# Comunicacao.net
KiCad netlist of a schematic drawn in Altium Designer
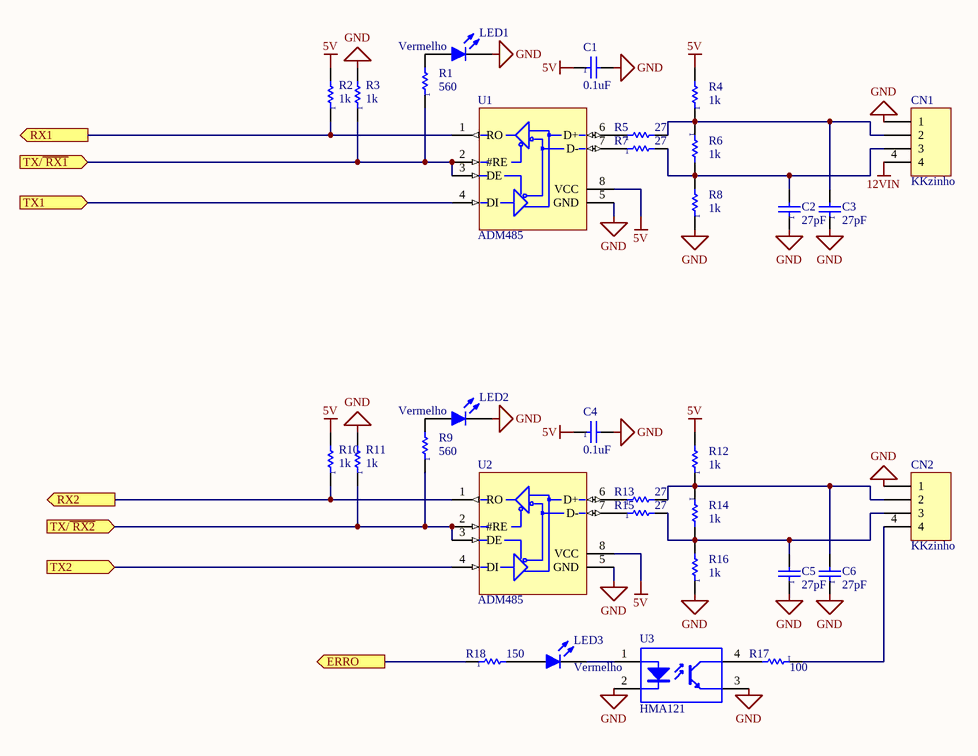
[diagram p0: Comunicacao.SchDoc]

(export (version "E")
  (design (tool "Eeschema 10.0.6"))
  (components
    (comp (ref "C1")
      (value "0.1uF")
      (footprint "SMD_0805")
      (description "Capacitor")
      (fields (field (name "MANUFACTURER") "Generic Components"))
      (libsource (lib "comps_passivos") (part "Cap"))
    )
    (comp (ref "C2")
      (value "27pF")
      (footprint "SMD_0805")
      (description "Capacitor")
      (fields (field (name "MANUFACTURER") "Generic Components"))
      (libsource (lib "comps_passivos") (part "Cap"))
    )
    (comp (ref "C3")
      (value "27pF")
      (footprint "SMD_0805")
      (description "Capacitor")
      (fields (field (name "MANUFACTURER") "Generic Components"))
      (libsource (lib "comps_passivos") (part "Cap"))
    )
    (comp (ref "C4")
      (value "0.1uF")
      (footprint "SMD_0805")
      (description "Capacitor")
      (fields (field (name "MANUFACTURER") "Generic Components"))
      (libsource (lib "comps_passivos") (part "Cap"))
    )
    (comp (ref "C5")
      (value "27pF")
      (footprint "SMD_0805")
      (description "Capacitor")
      (fields (field (name "MANUFACTURER") "Generic Components"))
      (libsource (lib "comps_passivos") (part "Cap"))
    )
    (comp (ref "C6")
      (value "27pF")
      (footprint "SMD_0805")
      (description "Capacitor")
      (fields (field (name "MANUFACTURER") "Generic Components"))
      (libsource (lib "comps_passivos") (part "Cap"))
    )
    (comp (ref "CN1")
      (value "KKzinho")
      (footprint "KK4 - 2.54mm")
      (description "Conector Linear tipo KK de 4 vias")
      (libsource (lib "conectores") (part "KK4"))
    )
    (comp (ref "CN2")
      (value "KKzinho")
      (footprint "KK4 - 2.54mm")
      (description "Conector Linear tipo KK de 4 vias")
      (libsource (lib "conectores") (part "KK4"))
    )
    (comp (ref "LED1")
      (value "Vermelho")
      (footprint "LED_SMD_0805")
      (description "Led")
      (fields (field (name "MANUFACTURER") "Generic Components") (field (name "PUBLISHER") "Altium Limited"))
      (libsource (lib "diodos_transistores") (part "Led"))
    )
    (comp (ref "LED2")
      (value "Vermelho")
      (footprint "LED_SMD_0805")
      (description "Led")
      (fields (field (name "MANUFACTURER") "Generic Components") (field (name "PUBLISHER") "Altium Limited"))
      (libsource (lib "diodos_transistores") (part "Led"))
    )
    (comp (ref "LED3")
      (value "Vermelho")
      (footprint "LED_SMD_0805")
      (description "Led")
      (fields (field (name "MANUFACTURER") "Generic Components") (field (name "PUBLISHER") "Altium Limited"))
      (libsource (lib "diodos_transistores") (part "Led"))
    )
    (comp (ref "R1")
      (value "560")
      (footprint "SMD_0805")
      (description "Resistor")
      (libsource (lib "passivos") (part "Res"))
    )
    (comp (ref "R2")
      (value "1k")
      (footprint "SMD_0805")
      (description "Resistor")
      (libsource (lib "passivos") (part "Res"))
    )
    (comp (ref "R3")
      (value "1k")
      (footprint "SMD_0805")
      (description "Resistor")
      (libsource (lib "passivos") (part "Resistor"))
    )
    (comp (ref "R4")
      (value "1k")
      (footprint "SMD_0805")
      (description "Resistor")
      (libsource (lib "passivos") (part "Resistor"))
    )
    (comp (ref "R5")
      (value "27")
      (footprint "SMD_0805")
      (description "Resistor")
      (libsource (lib "passivos") (part "Resistor"))
    )
    (comp (ref "R6")
      (value "1k")
      (footprint "SMD_0805")
      (description "Resistor")
      (libsource (lib "passivos") (part "Resistor"))
    )
    (comp (ref "R7")
      (value "27")
      (footprint "SMD_0805")
      (description "Resistor")
      (libsource (lib "passivos") (part "Resistor"))
    )
    (comp (ref "R8")
      (value "1k")
      (footprint "SMD_0805")
      (description "Resistor")
      (libsource (lib "passivos") (part "Resistor"))
    )
    (comp (ref "R9")
      (value "560")
      (footprint "SMD_0805")
      (description "Resistor")
      (libsource (lib "passivos") (part "Res"))
    )
    (comp (ref "R10")
      (value "1k")
      (footprint "SMD_0805")
      (description "Resistor")
      (libsource (lib "passivos") (part "Res"))
    )
    (comp (ref "R11")
      (value "1k")
      (footprint "SMD_0805")
      (description "Resistor")
      (libsource (lib "passivos") (part "Resistor"))
    )
    (comp (ref "R12")
      (value "1k")
      (footprint "SMD_0805")
      (description "Resistor")
      (libsource (lib "passivos") (part "Resistor"))
    )
    (comp (ref "R13")
      (value "27")
      (footprint "SMD_0805")
      (description "Resistor")
      (libsource (lib "passivos") (part "Resistor"))
    )
    (comp (ref "R14")
      (value "1k")
      (footprint "SMD_0805")
      (description "Resistor")
      (libsource (lib "passivos") (part "Resistor"))
    )
    (comp (ref "R15")
      (value "27")
      (footprint "SMD_0805")
      (description "Resistor")
      (libsource (lib "passivos") (part "Resistor"))
    )
    (comp (ref "R16")
      (value "1k")
      (footprint "SMD_0805")
      (description "Resistor")
      (libsource (lib "passivos") (part "Resistor"))
    )
    (comp (ref "R17")
      (value "100")
      (footprint "SMD_0805")
      (description "Resistor")
      (libsource (lib "passivos") (part "Resistor"))
    )
    (comp (ref "R18")
      (value "150")
      (footprint "SMD_0805")
      (description "Resistor")
      (libsource (lib "passivos") (part "Resistor"))
    )
    (comp (ref "U1")
      (value "ADM485")
      (footprint "SO-8_SO-G8/E2.5")
      (description "Differential bus transceiver (MAX485 - SN75176)")
      (libsource (lib "cis_digitais") (part "RS485"))
    )
    (comp (ref "U2")
      (value "ADM485")
      (footprint "SO-8_SO-G8/E2.5")
      (description "Differential bus transceiver (MAX485 - SN75176)")
      (libsource (lib "cis_digitais") (part "RS485"))
    )
    (comp (ref "U3")
      (value "HMA121")
      (footprint "SO4")
      (description "Phototransistor Optocoupler SMD full Pptch mini-flat type")
      (fields (field (name "MANUFACTURER") "Generic Components") (field (name "PUBLISHER") "Altium Limited"))
      (libsource (lib "diodos_transistores") (part "HMA"))
    )
  )
  (nets
    (net (code "1") (name "/ERRO") (class "Default")
      (node (ref "R18") (pin "1") (pinfunction "1_1") (pintype "passive"))
    )
    (net (code "2") (name "/RX1") (class "Default")
      (node (ref "R2") (pin "1") (pinfunction "1_1") (pintype "passive"))
      (node (ref "U1") (pin "1") (pinfunction "RO_1") (pintype "output"))
    )
    (net (code "3") (name "/RX2") (class "Default")
      (node (ref "R10") (pin "1") (pinfunction "1_1") (pintype "passive"))
      (node (ref "U2") (pin "1") (pinfunction "RO_1") (pintype "output"))
    )
    (net (code "4") (name "/TX1") (class "Default")
      (node (ref "U1") (pin "4") (pinfunction "DI_4") (pintype "input"))
    )
    (net (code "5") (name "/TX2") (class "Default")
      (node (ref "U2") (pin "4") (pinfunction "DI_4") (pintype "input"))
    )
    (net (code "6") (name "/TX{slash}~{ RX1}") (class "Default")
      (node (ref "R1") (pin "1") (pinfunction "1_1") (pintype "passive"))
      (node (ref "R3") (pin "1") (pinfunction "1_1") (pintype "passive"))
      (node (ref "U1") (pin "2") (pinfunction "#RE_2") (pintype "input"))
      (node (ref "U1") (pin "3") (pinfunction "DE_3") (pintype "input"))
    )
    (net (code "7") (name "/TX{slash}~{ RX2}") (class "Default")
      (node (ref "R11") (pin "1") (pinfunction "1_1") (pintype "passive"))
      (node (ref "R9") (pin "1") (pinfunction "1_1") (pintype "passive"))
      (node (ref "U2") (pin "2") (pinfunction "#RE_2") (pintype "input"))
      (node (ref "U2") (pin "3") (pinfunction "DE_3") (pintype "input"))
    )
    (net (code "8") (name "5V") (class "Default")
      (node (ref "C1") (pin "1") (pinfunction "1_1") (pintype "passive"))
      (node (ref "C4") (pin "1") (pinfunction "1_1") (pintype "passive"))
      (node (ref "R10") (pin "2") (pinfunction "2_2") (pintype "passive"))
      (node (ref "R12") (pin "2") (pinfunction "2_2") (pintype "passive"))
      (node (ref "R2") (pin "2") (pinfunction "2_2") (pintype "passive"))
      (node (ref "R4") (pin "2") (pinfunction "2_2") (pintype "passive"))
      (node (ref "U1") (pin "8") (pinfunction "VCC_8") (pintype "power_in"))
      (node (ref "U2") (pin "8") (pinfunction "VCC_8") (pintype "power_in"))
    )
    (net (code "9") (name "12VIN") (class "Default")
      (node (ref "CN1") (pin "4") (pinfunction "4_4") (pintype "passive"))
    )
    (net (code "10") (name "GND") (class "Default")
      (node (ref "C1") (pin "2") (pinfunction "2_2") (pintype "passive"))
      (node (ref "C2") (pin "1") (pinfunction "1_1") (pintype "passive"))
      (node (ref "C3") (pin "1") (pinfunction "1_1") (pintype "passive"))
      (node (ref "C4") (pin "2") (pinfunction "2_2") (pintype "passive"))
      (node (ref "C5") (pin "1") (pinfunction "1_1") (pintype "passive"))
      (node (ref "C6") (pin "1") (pinfunction "1_1") (pintype "passive"))
      (node (ref "CN1") (pin "1") (pinfunction "1_1") (pintype "passive"))
      (node (ref "CN2") (pin "1") (pinfunction "1_1") (pintype "passive"))
      (node (ref "LED1") (pin "2") (pinfunction "K_2") (pintype "passive"))
      (node (ref "LED2") (pin "2") (pinfunction "K_2") (pintype "passive"))
      (node (ref "R11") (pin "2") (pinfunction "2_2") (pintype "passive"))
      (node (ref "R16") (pin "1") (pinfunction "1_1") (pintype "passive"))
      (node (ref "R3") (pin "2") (pinfunction "2_2") (pintype "passive"))
      (node (ref "R8") (pin "1") (pinfunction "1_1") (pintype "passive"))
      (node (ref "U1") (pin "5") (pinfunction "GND_5") (pintype "power_in"))
      (node (ref "U2") (pin "5") (pinfunction "GND_5") (pintype "power_in"))
      (node (ref "U3") (pin "2") (pinfunction "K_2") (pintype "passive"))
      (node (ref "U3") (pin "3") (pinfunction "E_3") (pintype "passive"))
    )
    (net (code "11") (name "Net-(C2-Pad2)") (class "Default")
      (node (ref "C2") (pin "2") (pinfunction "2_2") (pintype "passive"))
      (node (ref "CN1") (pin "3") (pinfunction "3_3") (pintype "passive"))
      (node (ref "R6") (pin "2") (pinfunction "2_2") (pintype "passive"))
      (node (ref "R7") (pin "2") (pinfunction "2_2") (pintype "passive"))
      (node (ref "R8") (pin "2") (pinfunction "2_2") (pintype "passive"))
    )
    (net (code "12") (name "Net-(C3-Pad2)") (class "Default")
      (node (ref "C3") (pin "2") (pinfunction "2_2") (pintype "passive"))
      (node (ref "CN1") (pin "2") (pinfunction "2_2") (pintype "passive"))
      (node (ref "R4") (pin "1") (pinfunction "1_1") (pintype "passive"))
      (node (ref "R5") (pin "2") (pinfunction "2_2") (pintype "passive"))
      (node (ref "R6") (pin "1") (pinfunction "1_1") (pintype "passive"))
    )
    (net (code "13") (name "Net-(C5-Pad2)") (class "Default")
      (node (ref "C5") (pin "2") (pinfunction "2_2") (pintype "passive"))
      (node (ref "CN2") (pin "3") (pinfunction "3_3") (pintype "passive"))
      (node (ref "R14") (pin "2") (pinfunction "2_2") (pintype "passive"))
      (node (ref "R15") (pin "2") (pinfunction "2_2") (pintype "passive"))
      (node (ref "R16") (pin "2") (pinfunction "2_2") (pintype "passive"))
    )
    (net (code "14") (name "Net-(C6-Pad2)") (class "Default")
      (node (ref "C6") (pin "2") (pinfunction "2_2") (pintype "passive"))
      (node (ref "CN2") (pin "2") (pinfunction "2_2") (pintype "passive"))
      (node (ref "R12") (pin "1") (pinfunction "1_1") (pintype "passive"))
      (node (ref "R13") (pin "2") (pinfunction "2_2") (pintype "passive"))
      (node (ref "R14") (pin "1") (pinfunction "1_1") (pintype "passive"))
    )
    (net (code "15") (name "Net-(CN2-Pad4)") (class "Default")
      (node (ref "CN2") (pin "4") (pinfunction "4_4") (pintype "passive"))
      (node (ref "R17") (pin "1") (pinfunction "1_1") (pintype "passive"))
    )
    (net (code "16") (name "Net-(LED1-A)") (class "Default")
      (node (ref "LED1") (pin "1") (pinfunction "A_1") (pintype "passive"))
      (node (ref "R1") (pin "2") (pinfunction "2_2") (pintype "passive"))
    )
    (net (code "17") (name "Net-(LED2-A)") (class "Default")
      (node (ref "LED2") (pin "1") (pinfunction "A_1") (pintype "passive"))
      (node (ref "R9") (pin "2") (pinfunction "2_2") (pintype "passive"))
    )
    (net (code "18") (name "Net-(LED3-A)") (class "Default")
      (node (ref "LED3") (pin "1") (pinfunction "A_1") (pintype "passive"))
      (node (ref "R18") (pin "2") (pinfunction "2_2") (pintype "passive"))
    )
    (net (code "19") (name "Net-(LED3-K)") (class "Default")
      (node (ref "LED3") (pin "2") (pinfunction "K_2") (pintype "passive"))
      (node (ref "U3") (pin "1") (pinfunction "A_1") (pintype "passive"))
    )
    (net (code "20") (name "Net-(U1-D+)") (class "Default")
      (node (ref "R5") (pin "1") (pinfunction "1_1") (pintype "passive"))
      (node (ref "U1") (pin "6") (pinfunction "D+_6") (pintype "bidirectional"))
    )
    (net (code "21") (name "Net-(U1-D-)") (class "Default")
      (node (ref "R7") (pin "1") (pinfunction "1_1") (pintype "passive"))
      (node (ref "U1") (pin "7") (pinfunction "D-_7") (pintype "bidirectional"))
    )
    (net (code "22") (name "Net-(U2-D+)") (class "Default")
      (node (ref "R13") (pin "1") (pinfunction "1_1") (pintype "passive"))
      (node (ref "U2") (pin "6") (pinfunction "D+_6") (pintype "bidirectional"))
    )
    (net (code "23") (name "Net-(U2-D-)") (class "Default")
      (node (ref "R15") (pin "1") (pinfunction "1_1") (pintype "passive"))
      (node (ref "U2") (pin "7") (pinfunction "D-_7") (pintype "bidirectional"))
    )
    (net (code "24") (name "Net-(U3-C)") (class "Default")
      (node (ref "R17") (pin "2") (pinfunction "2_2") (pintype "passive"))
      (node (ref "U3") (pin "4") (pinfunction "C_4") (pintype "passive"))
    )
  )
)
